# CAP_MATRIX_OUT.net
KiCad netlist of a schematic drawn in Altium Designer
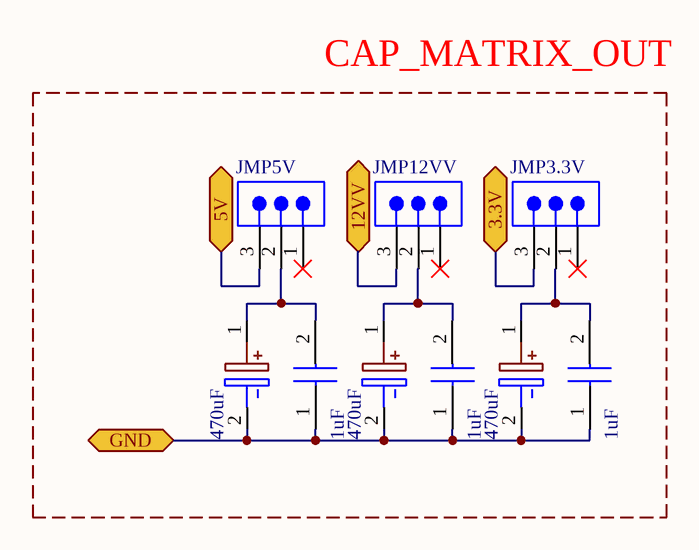
[diagram p0: CAP_MATRIX_OUT.SchDoc]

(export (version "E")
  (design (tool "Eeschema 10.0.6"))
  (components
    (comp (ref "CAPCE5")
      (value "1uF")
      (footprint "К10-17Б")
      (description "К10-17Б")
      (libsource (lib "Components_Robots") (part "CAP"))
    )
    (comp (ref "CAPCE6")
      (value "1uF")
      (footprint "К10-17Б")
      (description "К10-17Б")
      (libsource (lib "Components_Robots") (part "CAP"))
    )
    (comp (ref "CAPCE7")
      (value "1uF")
      (footprint "К10-17Б")
      (description "К10-17Б")
      (libsource (lib "Components_Robots") (part "CAP"))
    )
    (comp (ref "CAPEL5")
      (value "470uF")
      (footprint "CAP-12.5x13.5")
      (description "YUQINGXIN")
      (libsource (lib "Components_Robots") (part "CAP-12.5x13.5"))
    )
    (comp (ref "CAPEL6")
      (value "470uF")
      (footprint "CAP-12.5x13.5")
      (description "YUQINGXIN")
      (libsource (lib "Components_Robots") (part "CAP-12.5x13.5"))
    )
    (comp (ref "CAPEL7")
      (value "470uF")
      (footprint "CAP-12.5x13.5")
      (description "YUQINGXIN")
      (libsource (lib "Components_Robots") (part "CAP-12.5x13.5"))
    )
    (comp (ref "JMP3.3V")
      (value "JMP-03P")
      (footprint "JMP-03P")
      (description "PLS-1x3")
      (libsource (lib "Components_Robots") (part "JMP-03P"))
    )
    (comp (ref "JMP5V")
      (value "JMP-03P")
      (footprint "JMP-03P")
      (description "PLS-1x3")
      (libsource (lib "Components_Robots") (part "JMP-03P"))
    )
    (comp (ref "JMP12VV")
      (value "JMP-03P")
      (footprint "JMP-03P")
      (description "PLS-1x3")
      (libsource (lib "Components_Robots") (part "JMP-03P"))
    )
  )
  (nets
    (net (code "1") (name "/3.3V") (class "Default")
      (node (ref "JMP3.3V") (pin "3") (pinfunction "3_3") (pintype "passive"))
    )
    (net (code "2") (name "/5V") (class "Default")
      (node (ref "JMP5V") (pin "3") (pinfunction "3_3") (pintype "passive"))
    )
    (net (code "3") (name "/12VV") (class "Default")
      (node (ref "JMP12VV") (pin "3") (pinfunction "3_3") (pintype "passive"))
    )
    (net (code "4") (name "/GND") (class "Default")
      (node (ref "CAPCE5") (pin "1") (pinfunction "1_1") (pintype "passive"))
      (node (ref "CAPCE6") (pin "1") (pinfunction "1_1") (pintype "passive"))
      (node (ref "CAPCE7") (pin "1") (pinfunction "1_1") (pintype "passive"))
      (node (ref "CAPEL5") (pin "2") (pinfunction "-_2") (pintype "passive"))
      (node (ref "CAPEL6") (pin "2") (pinfunction "-_2") (pintype "passive"))
      (node (ref "CAPEL7") (pin "2") (pinfunction "-_2") (pintype "passive"))
    )
    (net (code "5") (name "Net-(CAPEL5-+)") (class "Default")
      (node (ref "CAPCE5") (pin "2") (pinfunction "2_2") (pintype "passive"))
      (node (ref "CAPEL5") (pin "1") (pinfunction "+_1") (pintype "passive"))
      (node (ref "JMP5V") (pin "2") (pinfunction "2_2") (pintype "passive"))
    )
    (net (code "6") (name "Net-(CAPEL6-+)") (class "Default")
      (node (ref "CAPCE6") (pin "2") (pinfunction "2_2") (pintype "passive"))
      (node (ref "CAPEL6") (pin "1") (pinfunction "+_1") (pintype "passive"))
      (node (ref "JMP12VV") (pin "2") (pinfunction "2_2") (pintype "passive"))
    )
    (net (code "7") (name "Net-(CAPEL7-+)") (class "Default")
      (node (ref "CAPCE7") (pin "2") (pinfunction "2_2") (pintype "passive"))
      (node (ref "CAPEL7") (pin "1") (pinfunction "+_1") (pintype "passive"))
      (node (ref "JMP3.3V") (pin "2") (pinfunction "2_2") (pintype "passive"))
    )
    (net (code "8") (name "unconnected-(JMP3.3V-Pad1)") (class "Default")
      (node (ref "JMP3.3V") (pin "1") (pinfunction "1_1") (pintype "passive+no_connect"))
    )
    (net (code "9") (name "unconnected-(JMP5V-Pad1)") (class "Default")
      (node (ref "JMP5V") (pin "1") (pinfunction "1_1") (pintype "passive+no_connect"))
    )
    (net (code "10") (name "unconnected-(JMP12VV-Pad1)") (class "Default")
      (node (ref "JMP12VV") (pin "1") (pinfunction "1_1") (pintype "passive+no_connect"))
    )
  )
)
